# hd-gs-alt.net
KiCad netlist of a schematic drawn in EAGLE
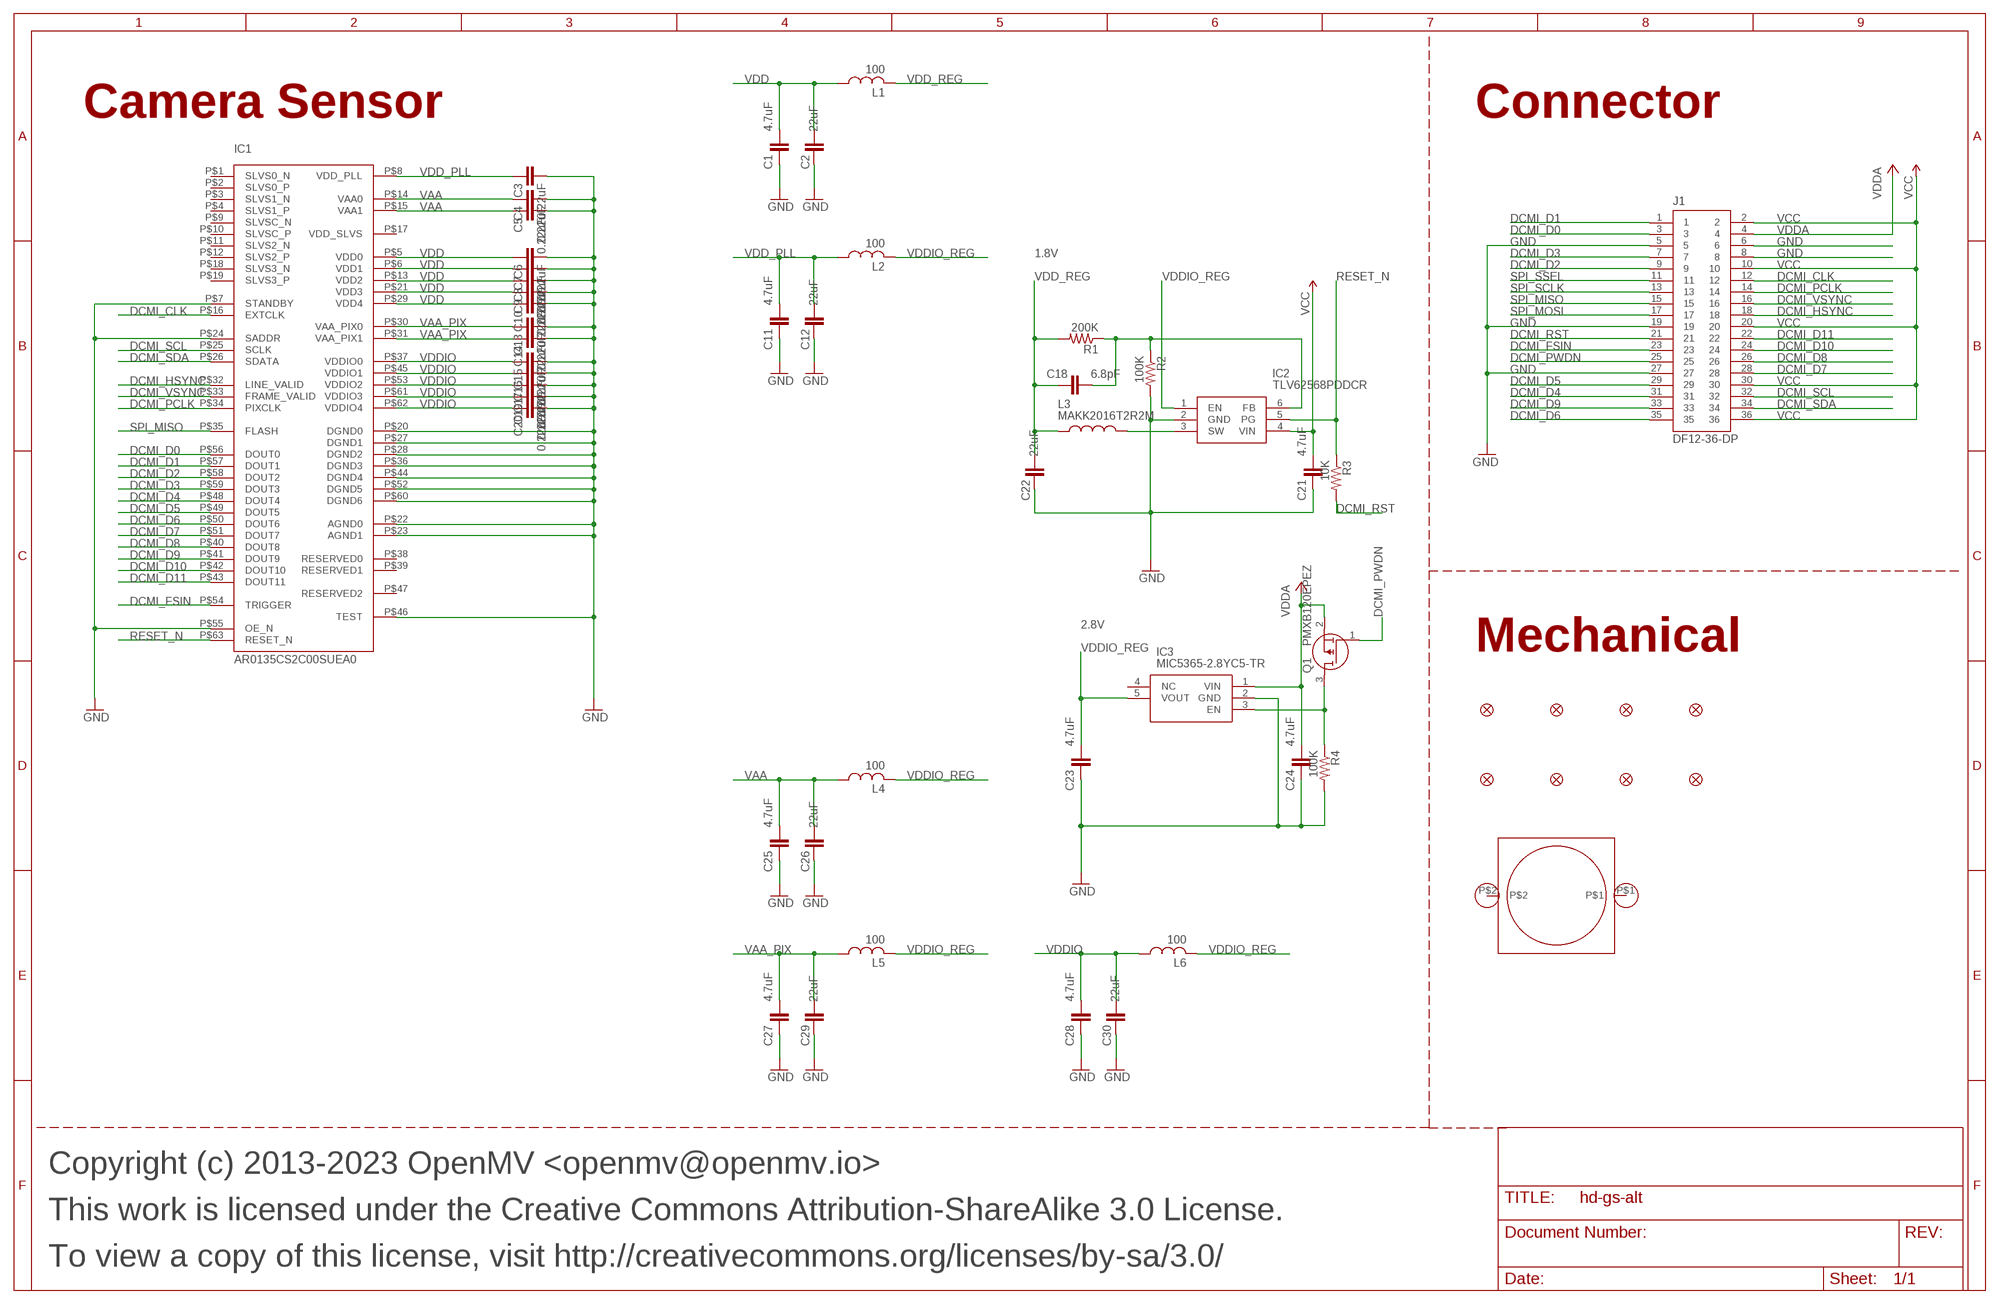
[diagram p0: schematic, sheet 1]

(export (version "E")
  (design (tool "Eeschema 10.0.6"))
  (components
    (comp (ref "C1")
      (value "4.7uF")
      (footprint "eagle-import:0402")
      (fields (field (name "MPN") "JMK105BBJ475MV-F"))
      (libsource (lib "eagle-import") (part "CAP_0402"))
    )
    (comp (ref "C2")
      (value "22uF")
      (footprint "eagle-import:0805")
      (fields (field (name "MPN") "CL21A226MQQNNNE"))
      (libsource (lib "eagle-import") (part "22UF-0805-6.3V-20%"))
    )
    (comp (ref "C3")
      (value "0.22uF")
      (footprint "eagle-import:C0201")
      (fields (field (name "MPN") "GRM033R60J224ME15D"))
      (libsource (lib "eagle-import") (part "C-EUC0201"))
    )
    (comp (ref "C4")
      (value "0.22uF")
      (footprint "eagle-import:C0201")
      (fields (field (name "MPN") "GRM033R60J224ME15D"))
      (libsource (lib "eagle-import") (part "C-EUC0201"))
    )
    (comp (ref "C5")
      (value "0.22uF")
      (footprint "eagle-import:C0201")
      (fields (field (name "MPN") "GRM033R60J224ME15D"))
      (libsource (lib "eagle-import") (part "C-EUC0201"))
    )
    (comp (ref "C6")
      (value "0.22uF")
      (footprint "eagle-import:C0201")
      (fields (field (name "MPN") "GRM033R60J224ME15D"))
      (libsource (lib "eagle-import") (part "C-EUC0201"))
    )
    (comp (ref "C7")
      (value "0.22uF")
      (footprint "eagle-import:C0201")
      (fields (field (name "MPN") "GRM033R60J224ME15D"))
      (libsource (lib "eagle-import") (part "C-EUC0201"))
    )
    (comp (ref "C8")
      (value "0.22uF")
      (footprint "eagle-import:C0201")
      (fields (field (name "MPN") "GRM033R60J224ME15D"))
      (libsource (lib "eagle-import") (part "C-EUC0201"))
    )
    (comp (ref "C9")
      (value "0.22uF")
      (footprint "eagle-import:C0201")
      (fields (field (name "MPN") "GRM033R60J224ME15D"))
      (libsource (lib "eagle-import") (part "C-EUC0201"))
    )
    (comp (ref "C10")
      (value "0.22uF")
      (footprint "eagle-import:C0201")
      (fields (field (name "MPN") "GRM033R60J224ME15D"))
      (libsource (lib "eagle-import") (part "C-EUC0201"))
    )
    (comp (ref "C11")
      (value "4.7uF")
      (footprint "eagle-import:0402")
      (fields (field (name "MPN") "JMK105BBJ475MV-F"))
      (libsource (lib "eagle-import") (part "CAP_0402"))
    )
    (comp (ref "C12")
      (value "22uF")
      (footprint "eagle-import:0805")
      (fields (field (name "MPN") "CL21A226MQQNNNE"))
      (libsource (lib "eagle-import") (part "22UF-0805-6.3V-20%"))
    )
    (comp (ref "C13")
      (value "0.22uF")
      (footprint "eagle-import:C0201")
      (fields (field (name "MPN") "GRM033R60J224ME15D"))
      (libsource (lib "eagle-import") (part "C-EUC0201"))
    )
    (comp (ref "C14")
      (value "0.22uF")
      (footprint "eagle-import:C0201")
      (fields (field (name "MPN") "GRM033R60J224ME15D"))
      (libsource (lib "eagle-import") (part "C-EUC0201"))
    )
    (comp (ref "C15")
      (value "0.22uF")
      (footprint "eagle-import:C0201")
      (fields (field (name "MPN") "GRM033R60J224ME15D"))
      (libsource (lib "eagle-import") (part "C-EUC0201"))
    )
    (comp (ref "C16")
      (value "0.22uF")
      (footprint "eagle-import:C0201")
      (fields (field (name "MPN") "GRM033R60J224ME15D"))
      (libsource (lib "eagle-import") (part "C-EUC0201"))
    )
    (comp (ref "C17")
      (value "0.22uF")
      (footprint "eagle-import:C0201")
      (fields (field (name "MPN") "GRM033R60J224ME15D"))
      (libsource (lib "eagle-import") (part "C-EUC0201"))
    )
    (comp (ref "C18")
      (value "6.8pF")
      (footprint "eagle-import:0402")
      (fields (field (name "MPN") "GRM1555C1H6R8DA01D"))
      (libsource (lib "eagle-import") (part "CAP_0402"))
    )
    (comp (ref "C19")
      (value "0.22uF")
      (footprint "eagle-import:C0201")
      (fields (field (name "MPN") "GRM033R60J224ME15D"))
      (libsource (lib "eagle-import") (part "C-EUC0201"))
    )
    (comp (ref "C20")
      (value "0.22uF")
      (footprint "eagle-import:C0201")
      (fields (field (name "MPN") "GRM033R60J224ME15D"))
      (libsource (lib "eagle-import") (part "C-EUC0201"))
    )
    (comp (ref "C21")
      (value "4.7uF")
      (footprint "eagle-import:0402")
      (fields (field (name "MPN") "JMK105BBJ475MV-F"))
      (libsource (lib "eagle-import") (part "CAP_0402"))
    )
    (comp (ref "C22")
      (value "22uF")
      (footprint "eagle-import:0805")
      (fields (field (name "MPN") "CL21A226MQQNNNE"))
      (libsource (lib "eagle-import") (part "22UF-0805-6.3V-20%"))
    )
    (comp (ref "C23")
      (value "4.7uF")
      (footprint "eagle-import:0402")
      (fields (field (name "MPN") "JMK105BBJ475MV-F"))
      (libsource (lib "eagle-import") (part "CAP_0402"))
    )
    (comp (ref "C24")
      (value "4.7uF")
      (footprint "eagle-import:0402")
      (fields (field (name "MPN") "JMK105BBJ475MV-F"))
      (libsource (lib "eagle-import") (part "CAP_0402"))
    )
    (comp (ref "C25")
      (value "4.7uF")
      (footprint "eagle-import:0402")
      (fields (field (name "MPN") "JMK105BBJ475MV-F"))
      (libsource (lib "eagle-import") (part "CAP_0402"))
    )
    (comp (ref "C26")
      (value "22uF")
      (footprint "eagle-import:0805")
      (fields (field (name "MPN") "CL21A226MQQNNNE"))
      (libsource (lib "eagle-import") (part "22UF-0805-6.3V-20%"))
    )
    (comp (ref "C27")
      (value "4.7uF")
      (footprint "eagle-import:0402")
      (fields (field (name "MPN") "JMK105BBJ475MV-F"))
      (libsource (lib "eagle-import") (part "CAP_0402"))
    )
    (comp (ref "C28")
      (value "4.7uF")
      (footprint "eagle-import:0402")
      (fields (field (name "MPN") "JMK105BBJ475MV-F"))
      (libsource (lib "eagle-import") (part "CAP_0402"))
    )
    (comp (ref "C29")
      (value "22uF")
      (footprint "eagle-import:0805")
      (fields (field (name "MPN") "CL21A226MQQNNNE"))
      (libsource (lib "eagle-import") (part "22UF-0805-6.3V-20%"))
    )
    (comp (ref "C30")
      (value "22uF")
      (footprint "eagle-import:0805")
      (fields (field (name "MPN") "CL21A226MQQNNNE"))
      (libsource (lib "eagle-import") (part "22UF-0805-6.3V-20%"))
    )
    (comp (ref "FD1")
      (value "FIDUCIAL1X2")
      (footprint "eagle-import:FIDUCIAL-1X2")
      (libsource (lib "eagle-import") (part "FIDUCIAL1X2"))
    )
    (comp (ref "FD2")
      (value "FIDUCIAL1X2")
      (footprint "eagle-import:FIDUCIAL-1X2")
      (libsource (lib "eagle-import") (part "FIDUCIAL1X2"))
    )
    (comp (ref "FD3")
      (value "FIDUCIAL1X2")
      (footprint "eagle-import:FIDUCIAL-1X2")
      (libsource (lib "eagle-import") (part "FIDUCIAL1X2"))
    )
    (comp (ref "FD4")
      (value "FIDUCIAL1X2")
      (footprint "eagle-import:FIDUCIAL-1X2")
      (libsource (lib "eagle-import") (part "FIDUCIAL1X2"))
    )
    (comp (ref "FD5")
      (value "FIDUCIAL1X2")
      (footprint "eagle-import:FIDUCIAL-1X2")
      (libsource (lib "eagle-import") (part "FIDUCIAL1X2"))
    )
    (comp (ref "FD6")
      (value "FIDUCIAL1X2")
      (footprint "eagle-import:FIDUCIAL-1X2")
      (libsource (lib "eagle-import") (part "FIDUCIAL1X2"))
    )
    (comp (ref "FD7")
      (value "FIDUCIAL1X2")
      (footprint "eagle-import:FIDUCIAL-1X2")
      (libsource (lib "eagle-import") (part "FIDUCIAL1X2"))
    )
    (comp (ref "FD8")
      (value "FIDUCIAL1X2")
      (footprint "eagle-import:FIDUCIAL-1X2")
      (libsource (lib "eagle-import") (part "FIDUCIAL1X2"))
    )
    (comp (ref "H1")
      (value "LENSMOUNT20MM")
      (footprint "eagle-import:LENSMOUNT-20MM")
      (libsource (lib "eagle-import") (part "LENSMOUNT20MM"))
    )
    (comp (ref "IC1")
      (value "AR0135CS2C00SUEA0")
      (footprint "eagle-import:AR0135CS2C00SUEA0")
      (fields (field (name "MPN") "AR0135CS2C00SUEA0-DRBR"))
      (libsource (lib "eagle-import") (part "AR0135CS2C00SUEA0"))
    )
    (comp (ref "IC2")
      (value "TLV62568PDDCR")
      (footprint "eagle-import:SOT95P280X110-6N")
      (fields (field (name "MOUSER_PART_NUMBER") "595-TLV62568PDDCR"))
      (libsource (lib "eagle-import") (part "TLV62568PDDCR"))
    )
    (comp (ref "IC3")
      (value "MIC5365-2.8YC5-TR")
      (footprint "eagle-import:SOT65P210X110-5N")
      (fields (field (name "MOUSER_PART_NUMBER") "998-MIC5365-2.8YC5TR"))
      (libsource (lib "eagle-import") (part "MIC5365-2.8YC5-TR"))
    )
    (comp (ref "J1")
      (value "DF12-36-DP")
      (footprint "eagle-import:DF12-36-DP")
      (fields (field (name "MPN") "DF12NB(3.0)-36DP-0.5V(51)"))
      (libsource (lib "eagle-import") (part "DF12-36-DP"))
    )
    (comp (ref "L1")
      (value "100")
      (footprint "eagle-import:0402")
      (fields (field (name "MPN") "MFBM1V1005-101-R"))
      (libsource (lib "eagle-import") (part "INDUCTOR_0402"))
    )
    (comp (ref "L2")
      (value "100")
      (footprint "eagle-import:0402")
      (fields (field (name "MPN") "MFBM1V1005-101-R"))
      (libsource (lib "eagle-import") (part "INDUCTOR_0402"))
    )
    (comp (ref "L3")
      (value "MAKK2016T2R2M")
      (footprint "eagle-import:INDC2016X100N")
      (fields (field (name "MF") "Taiyo Yuden"))
      (libsource (lib "eagle-import") (part "MAKK2016T2R2M"))
    )
    (comp (ref "L4")
      (value "100")
      (footprint "eagle-import:0402")
      (fields (field (name "MPN") "MFBM1V1005-101-R"))
      (libsource (lib "eagle-import") (part "INDUCTOR_0402"))
    )
    (comp (ref "L5")
      (value "100")
      (footprint "eagle-import:0402")
      (fields (field (name "MPN") "MFBM1V1005-101-R"))
      (libsource (lib "eagle-import") (part "INDUCTOR_0402"))
    )
    (comp (ref "L6")
      (value "100")
      (footprint "eagle-import:0402")
      (fields (field (name "MPN") "MFBM1V1005-101-R"))
      (libsource (lib "eagle-import") (part "INDUCTOR_0402"))
    )
    (comp (ref "Q1")
      (value "PMXB120EPEZ")
      (footprint "eagle-import:PMXB120EPEZ")
      (fields (field (name "MOUSER_PART_NUMBER") "771-PMXB120EPEZ"))
      (libsource (lib "eagle-import") (part "PMXB120EPEZ"))
    )
    (comp (ref "R1")
      (value "200K")
      (footprint "eagle-import:R0402")
      (fields (field (name "MPN") "CRCW0402200KFKEDC"))
      (libsource (lib "eagle-import") (part "R-US_R0402"))
    )
    (comp (ref "R2")
      (value "100K")
      (footprint "eagle-import:R0402")
      (fields (field (name "MPN") "AC0402FR-07100KL"))
      (libsource (lib "eagle-import") (part "R-US_R0402"))
    )
    (comp (ref "R3")
      (value "10K")
      (footprint "eagle-import:R0402")
      (fields (field (name "MPN") "AC0402FR-1310KL"))
      (libsource (lib "eagle-import") (part "R-US_R0402"))
    )
    (comp (ref "R4")
      (value "100K")
      (footprint "eagle-import:R0402")
      (fields (field (name "MPN") "AC0402FR-07100KL"))
      (libsource (lib "eagle-import") (part "R-US_R0402"))
    )
  )
  (nets
    (net (code "1") (name "/DCMI_CLK") (class "Default")
      (node (ref "IC1") (pin "P$16") (pinfunction "EXTCLK_P$16") (pintype "bidirectional"))
      (node (ref "J1") (pin "12") (pinfunction "12_12") (pintype "bidirectional"))
    )
    (net (code "2") (name "/DCMI_D0") (class "Default")
      (node (ref "IC1") (pin "P$56") (pinfunction "DOUT0_P$56") (pintype "bidirectional"))
      (node (ref "J1") (pin "3") (pinfunction "3_3") (pintype "bidirectional"))
    )
    (net (code "3") (name "/DCMI_D1") (class "Default")
      (node (ref "IC1") (pin "P$57") (pinfunction "DOUT1_P$57") (pintype "bidirectional"))
      (node (ref "J1") (pin "1") (pinfunction "1_1") (pintype "bidirectional"))
    )
    (net (code "4") (name "/DCMI_D2") (class "Default")
      (node (ref "IC1") (pin "P$58") (pinfunction "DOUT2_P$58") (pintype "bidirectional"))
      (node (ref "J1") (pin "9") (pinfunction "9_9") (pintype "bidirectional"))
    )
    (net (code "5") (name "/DCMI_D3") (class "Default")
      (node (ref "IC1") (pin "P$59") (pinfunction "DOUT3_P$59") (pintype "bidirectional"))
      (node (ref "J1") (pin "7") (pinfunction "7_7") (pintype "bidirectional"))
    )
    (net (code "6") (name "/DCMI_D4") (class "Default")
      (node (ref "IC1") (pin "P$48") (pinfunction "DOUT4_P$48") (pintype "bidirectional"))
      (node (ref "J1") (pin "31") (pinfunction "31_31") (pintype "bidirectional"))
    )
    (net (code "7") (name "/DCMI_D5") (class "Default")
      (node (ref "IC1") (pin "P$49") (pinfunction "DOUT5_P$49") (pintype "bidirectional"))
      (node (ref "J1") (pin "29") (pinfunction "29_29") (pintype "bidirectional"))
    )
    (net (code "8") (name "/DCMI_D6") (class "Default")
      (node (ref "IC1") (pin "P$50") (pinfunction "DOUT6_P$50") (pintype "bidirectional"))
      (node (ref "J1") (pin "35") (pinfunction "35_35") (pintype "bidirectional"))
    )
    (net (code "9") (name "/DCMI_D7") (class "Default")
      (node (ref "IC1") (pin "P$51") (pinfunction "DOUT7_P$51") (pintype "bidirectional"))
      (node (ref "J1") (pin "28") (pinfunction "28_28") (pintype "bidirectional"))
    )
    (net (code "10") (name "/DCMI_D8") (class "Default")
      (node (ref "IC1") (pin "P$40") (pinfunction "DOUT8_P$40") (pintype "bidirectional"))
      (node (ref "J1") (pin "26") (pinfunction "26_26") (pintype "bidirectional"))
    )
    (net (code "11") (name "/DCMI_D9") (class "Default")
      (node (ref "IC1") (pin "P$41") (pinfunction "DOUT9_P$41") (pintype "bidirectional"))
      (node (ref "J1") (pin "33") (pinfunction "33_33") (pintype "bidirectional"))
    )
    (net (code "12") (name "/DCMI_D10") (class "Default")
      (node (ref "IC1") (pin "P$42") (pinfunction "DOUT10_P$42") (pintype "bidirectional"))
      (node (ref "J1") (pin "24") (pinfunction "24_24") (pintype "bidirectional"))
    )
    (net (code "13") (name "/DCMI_D11") (class "Default")
      (node (ref "IC1") (pin "P$43") (pinfunction "DOUT11_P$43") (pintype "bidirectional"))
      (node (ref "J1") (pin "22") (pinfunction "22_22") (pintype "bidirectional"))
    )
    (net (code "14") (name "/DCMI_FSIN") (class "Default")
      (node (ref "IC1") (pin "P$54") (pinfunction "TRIGGER_P$54") (pintype "bidirectional"))
      (node (ref "J1") (pin "23") (pinfunction "23_23") (pintype "bidirectional"))
    )
    (net (code "15") (name "/DCMI_HSYNC") (class "Default")
      (node (ref "IC1") (pin "P$32") (pinfunction "LINE_VALID_P$32") (pintype "bidirectional"))
      (node (ref "J1") (pin "18") (pinfunction "18_18") (pintype "bidirectional"))
    )
    (net (code "16") (name "/DCMI_PCLK") (class "Default")
      (node (ref "IC1") (pin "P$34") (pinfunction "PIXCLK_P$34") (pintype "bidirectional"))
      (node (ref "J1") (pin "14") (pinfunction "14_14") (pintype "bidirectional"))
    )
    (net (code "17") (name "/DCMI_PWDN") (class "Default")
      (node (ref "J1") (pin "25") (pinfunction "25_25") (pintype "bidirectional"))
      (node (ref "Q1") (pin "1") (pinfunction "G_1") (pintype "bidirectional"))
    )
    (net (code "18") (name "/DCMI_RST") (class "Default")
      (node (ref "J1") (pin "21") (pinfunction "21_21") (pintype "bidirectional"))
      (node (ref "R3") (pin "2") (pinfunction "2_2") (pintype "passive"))
    )
    (net (code "19") (name "/DCMI_SCL") (class "Default")
      (node (ref "IC1") (pin "P$25") (pinfunction "SCLK_P$25") (pintype "bidirectional"))
      (node (ref "J1") (pin "32") (pinfunction "32_32") (pintype "bidirectional"))
    )
    (net (code "20") (name "/DCMI_SDA") (class "Default")
      (node (ref "IC1") (pin "P$26") (pinfunction "SDATA_P$26") (pintype "bidirectional"))
      (node (ref "J1") (pin "34") (pinfunction "34_34") (pintype "bidirectional"))
    )
    (net (code "21") (name "/DCMI_VSYNC") (class "Default")
      (node (ref "IC1") (pin "P$33") (pinfunction "FRAME_VALID_P$33") (pintype "bidirectional"))
      (node (ref "J1") (pin "16") (pinfunction "16_16") (pintype "bidirectional"))
    )
    (net (code "22") (name "/P$1") (class "Default")
      (node (ref "H1") (pin "P$1") (pinfunction "P$1_P$1") (pintype "power_in"))
    )
    (net (code "23") (name "/P$2") (class "Default")
      (node (ref "H1") (pin "P$2") (pinfunction "P$2_P$2") (pintype "power_in"))
    )
    (net (code "24") (name "/RESET_N") (class "Default")
      (node (ref "IC1") (pin "P$63") (pinfunction "RESET_N_P$63") (pintype "bidirectional"))
      (node (ref "IC2") (pin "5") (pinfunction "PG_5") (pintype "bidirectional"))
      (node (ref "R3") (pin "1") (pinfunction "1_1") (pintype "passive"))
    )
    (net (code "25") (name "/SPI_MISO") (class "Default")
      (node (ref "IC1") (pin "P$35") (pinfunction "FLASH_P$35") (pintype "bidirectional"))
      (node (ref "J1") (pin "15") (pinfunction "15_15") (pintype "bidirectional"))
    )
    (net (code "26") (name "/SPI_MOSI") (class "Default")
      (node (ref "J1") (pin "17") (pinfunction "17_17") (pintype "bidirectional"))
    )
    (net (code "27") (name "/SPI_SCLK") (class "Default")
      (node (ref "J1") (pin "13") (pinfunction "13_13") (pintype "bidirectional"))
    )
    (net (code "28") (name "/SPI_SSEL") (class "Default")
      (node (ref "J1") (pin "11") (pinfunction "11_11") (pintype "bidirectional"))
    )
    (net (code "29") (name "/VAA") (class "Default")
      (node (ref "C25") (pin "2") (pinfunction "2_2") (pintype "passive"))
      (node (ref "C26") (pin "2") (pinfunction "2_2") (pintype "passive"))
      (node (ref "C4") (pin "1") (pinfunction "1_1") (pintype "passive"))
      (node (ref "C5") (pin "1") (pinfunction "1_1") (pintype "passive"))
      (node (ref "IC1") (pin "P$14") (pinfunction "VAA0_P$14") (pintype "bidirectional"))
      (node (ref "IC1") (pin "P$15") (pinfunction "VAA1_P$15") (pintype "bidirectional"))
      (node (ref "L4") (pin "1") (pinfunction "P$1_1") (pintype "passive"))
    )
    (net (code "30") (name "/VAA_PIX") (class "Default")
      (node (ref "C13") (pin "1") (pinfunction "1_1") (pintype "passive"))
      (node (ref "C14") (pin "1") (pinfunction "1_1") (pintype "passive"))
      (node (ref "C27") (pin "2") (pinfunction "2_2") (pintype "passive"))
      (node (ref "C29") (pin "2") (pinfunction "2_2") (pintype "passive"))
      (node (ref "IC1") (pin "P$30") (pinfunction "VAA_PIX0_P$30") (pintype "bidirectional"))
      (node (ref "IC1") (pin "P$31") (pinfunction "VAA_PIX1_P$31") (pintype "bidirectional"))
      (node (ref "L5") (pin "1") (pinfunction "P$1_1") (pintype "passive"))
    )
    (net (code "31") (name "/VDD") (class "Default")
      (node (ref "C1") (pin "2") (pinfunction "2_2") (pintype "passive"))
      (node (ref "C10") (pin "1") (pinfunction "1_1") (pintype "passive"))
      (node (ref "C2") (pin "2") (pinfunction "2_2") (pintype "passive"))
      (node (ref "C6") (pin "1") (pinfunction "1_1") (pintype "passive"))
      (node (ref "C7") (pin "1") (pinfunction "1_1") (pintype "passive"))
      (node (ref "C8") (pin "1") (pinfunction "1_1") (pintype "passive"))
      (node (ref "C9") (pin "1") (pinfunction "1_1") (pintype "passive"))
      (node (ref "IC1") (pin "P$13") (pinfunction "VDD2_P$13") (pintype "bidirectional"))
      (node (ref "IC1") (pin "P$21") (pinfunction "VDD3_P$21") (pintype "bidirectional"))
      (node (ref "IC1") (pin "P$29") (pinfunction "VDD4_P$29") (pintype "bidirectional"))
      (node (ref "IC1") (pin "P$5") (pinfunction "VDD0_P$5") (pintype "bidirectional"))
      (node (ref "IC1") (pin "P$6") (pinfunction "VDD1_P$6") (pintype "bidirectional"))
      (node (ref "L1") (pin "1") (pinfunction "P$1_1") (pintype "passive"))
    )
    (net (code "32") (name "/VDDIO") (class "Default")
      (node (ref "C15") (pin "1") (pinfunction "1_1") (pintype "passive"))
      (node (ref "C16") (pin "1") (pinfunction "1_1") (pintype "passive"))
      (node (ref "C17") (pin "1") (pinfunction "1_1") (pintype "passive"))
      (node (ref "C19") (pin "1") (pinfunction "1_1") (pintype "passive"))
      (node (ref "C20") (pin "1") (pinfunction "1_1") (pintype "passive"))
      (node (ref "C28") (pin "2") (pinfunction "2_2") (pintype "passive"))
      (node (ref "C30") (pin "2") (pinfunction "2_2") (pintype "passive"))
      (node (ref "IC1") (pin "P$37") (pinfunction "VDDIO0_P$37") (pintype "bidirectional"))
      (node (ref "IC1") (pin "P$45") (pinfunction "VDDIO1_P$45") (pintype "bidirectional"))
      (node (ref "IC1") (pin "P$53") (pinfunction "VDDIO2_P$53") (pintype "bidirectional"))
      (node (ref "IC1") (pin "P$61") (pinfunction "VDDIO3_P$61") (pintype "bidirectional"))
      (node (ref "IC1") (pin "P$62") (pinfunction "VDDIO4_P$62") (pintype "bidirectional"))
      (node (ref "L6") (pin "1") (pinfunction "P$1_1") (pintype "passive"))
    )
    (net (code "33") (name "/VDDIO_REG") (class "Default")
      (node (ref "C23") (pin "2") (pinfunction "2_2") (pintype "passive"))
      (node (ref "IC2") (pin "1") (pinfunction "EN_1") (pintype "bidirectional"))
      (node (ref "IC3") (pin "5") (pinfunction "VOUT_5") (pintype "bidirectional"))
      (node (ref "L2") (pin "2") (pinfunction "P$2_2") (pintype "passive"))
      (node (ref "L4") (pin "2") (pinfunction "P$2_2") (pintype "passive"))
      (node (ref "L5") (pin "2") (pinfunction "P$2_2") (pintype "passive"))
      (node (ref "L6") (pin "2") (pinfunction "P$2_2") (pintype "passive"))
    )
    (net (code "34") (name "/VDD_PLL") (class "Default")
      (node (ref "C11") (pin "2") (pinfunction "2_2") (pintype "passive"))
      (node (ref "C12") (pin "2") (pinfunction "2_2") (pintype "passive"))
      (node (ref "C3") (pin "1") (pinfunction "1_1") (pintype "passive"))
      (node (ref "IC1") (pin "P$8") (pinfunction "VDD_PLL_P$8") (pintype "bidirectional"))
      (node (ref "L2") (pin "1") (pinfunction "P$1_1") (pintype "passive"))
    )
    (net (code "35") (name "/VDD_REG") (class "Default")
      (node (ref "C18") (pin "1") (pinfunction "1_1") (pintype "passive"))
      (node (ref "C22") (pin "2") (pinfunction "2_2") (pintype "passive"))
      (node (ref "L1") (pin "2") (pinfunction "P$2_2") (pintype "passive"))
      (node (ref "L3") (pin "1") (pinfunction "1_1") (pintype "passive"))
      (node (ref "R1") (pin "2") (pinfunction "2_2") (pintype "passive"))
    )
    (net (code "36") (name "GND") (class "Default")
      (node (ref "C1") (pin "1") (pinfunction "1_1") (pintype "passive"))
      (node (ref "C10") (pin "2") (pinfunction "2_2") (pintype "passive"))
      (node (ref "C11") (pin "1") (pinfunction "1_1") (pintype "passive"))
      (node (ref "C12") (pin "1") (pinfunction "1_1") (pintype "passive"))
      (node (ref "C13") (pin "2") (pinfunction "2_2") (pintype "passive"))
      (node (ref "C14") (pin "2") (pinfunction "2_2") (pintype "passive"))
      (node (ref "C15") (pin "2") (pinfunction "2_2") (pintype "passive"))
      (node (ref "C16") (pin "2") (pinfunction "2_2") (pintype "passive"))
      (node (ref "C17") (pin "2") (pinfunction "2_2") (pintype "passive"))
      (node (ref "C19") (pin "2") (pinfunction "2_2") (pintype "passive"))
      (node (ref "C2") (pin "1") (pinfunction "1_1") (pintype "passive"))
      (node (ref "C20") (pin "2") (pinfunction "2_2") (pintype "passive"))
      (node (ref "C21") (pin "1") (pinfunction "1_1") (pintype "passive"))
      (node (ref "C22") (pin "1") (pinfunction "1_1") (pintype "passive"))
      (node (ref "C23") (pin "1") (pinfunction "1_1") (pintype "passive"))
      (node (ref "C24") (pin "1") (pinfunction "1_1") (pintype "passive"))
      (node (ref "C25") (pin "1") (pinfunction "1_1") (pintype "passive"))
      (node (ref "C26") (pin "1") (pinfunction "1_1") (pintype "passive"))
      (node (ref "C27") (pin "1") (pinfunction "1_1") (pintype "passive"))
      (node (ref "C28") (pin "1") (pinfunction "1_1") (pintype "passive"))
      (node (ref "C29") (pin "1") (pinfunction "1_1") (pintype "passive"))
      (node (ref "C3") (pin "2") (pinfunction "2_2") (pintype "passive"))
      (node (ref "C30") (pin "1") (pinfunction "1_1") (pintype "passive"))
      (node (ref "C4") (pin "2") (pinfunction "2_2") (pintype "passive"))
      (node (ref "C5") (pin "2") (pinfunction "2_2") (pintype "passive"))
      (node (ref "C6") (pin "2") (pinfunction "2_2") (pintype "passive"))
      (node (ref "C7") (pin "2") (pinfunction "2_2") (pintype "passive"))
      (node (ref "C8") (pin "2") (pinfunction "2_2") (pintype "passive"))
      (node (ref "C9") (pin "2") (pinfunction "2_2") (pintype "passive"))
      (node (ref "IC1") (pin "P$20") (pinfunction "DGND0_P$20") (pintype "bidirectional"))
      (node (ref "IC1") (pin "P$22") (pinfunction "AGND0_P$22") (pintype "bidirectional"))
      (node (ref "IC1") (pin "P$23") (pinfunction "AGND1_P$23") (pintype "bidirectional"))
      (node (ref "IC1") (pin "P$24") (pinfunction "SADDR_P$24") (pintype "bidirectional"))
      (node (ref "IC1") (pin "P$27") (pinfunction "DGND1_P$27") (pintype "bidirectional"))
      (node (ref "IC1") (pin "P$28") (pinfunction "DGND2_P$28") (pintype "bidirectional"))
      (node (ref "IC1") (pin "P$36") (pinfunction "DGND3_P$36") (pintype "bidirectional"))
      (node (ref "IC1") (pin "P$44") (pinfunction "DGND4_P$44") (pintype "bidirectional"))
      (node (ref "IC1") (pin "P$46") (pinfunction "TEST_P$46") (pintype "bidirectional"))
      (node (ref "IC1") (pin "P$52") (pinfunction "DGND5_P$52") (pintype "bidirectional"))
      (node (ref "IC1") (pin "P$55") (pinfunction "OE_N_P$55") (pintype "bidirectional"))
      (node (ref "IC1") (pin "P$60") (pinfunction "DGND6_P$60") (pintype "bidirectional"))
      (node (ref "IC1") (pin "P$7") (pinfunction "STANDBY_P$7") (pintype "bidirectional"))
      (node (ref "IC2") (pin "2") (pinfunction "GND_2") (pintype "bidirectional"))
      (node (ref "IC3") (pin "2") (pinfunction "GND_2") (pintype "bidirectional"))
      (node (ref "J1") (pin "19") (pinfunction "19_19") (pintype "bidirectional"))
      (node (ref "J1") (pin "27") (pinfunction "27_27") (pintype "bidirectional"))
      (node (ref "J1") (pin "5") (pinfunction "5_5") (pintype "bidirectional"))
      (node (ref "J1") (pin "6") (pinfunction "6_6") (pintype "bidirectional"))
      (node (ref "J1") (pin "8") (pinfunction "8_8") (pintype "bidirectional"))
      (node (ref "R2") (pin "2") (pinfunction "2_2") (pintype "passive"))
      (node (ref "R4") (pin "2") (pinfunction "2_2") (pintype "passive"))
    )
    (net (code "37") (name "Net-(IC2-FB)") (class "Default")
      (node (ref "C18") (pin "2") (pinfunction "2_2") (pintype "passive"))
      (node (ref "IC2") (pin "6") (pinfunction "FB_6") (pintype "bidirectional"))
      (node (ref "R1") (pin "1") (pinfunction "1_1") (pintype "passive"))
      (node (ref "R2") (pin "1") (pinfunction "1_1") (pintype "passive"))
    )
    (net (code "38") (name "Net-(IC2-SW)") (class "Default")
      (node (ref "IC2") (pin "3") (pinfunction "SW_3") (pintype "bidirectional"))
      (node (ref "L3") (pin "2") (pinfunction "2_2") (pintype "passive"))
    )
    (net (code "39") (name "Net-(IC3-EN)") (class "Default")
      (node (ref "IC3") (pin "3") (pinfunction "EN_3") (pintype "bidirectional"))
      (node (ref "Q1") (pin "3") (pinfunction "D_3") (pintype "bidirectional"))
      (node (ref "R4") (pin "1") (pinfunction "1_1") (pintype "passive"))
    )
    (net (code "40") (name "VCC") (class "Default")
      (node (ref "C21") (pin "2") (pinfunction "2_2") (pintype "passive"))
      (node (ref "IC2") (pin "4") (pinfunction "VIN_4") (pintype "bidirectional"))
      (node (ref "J1") (pin "10") (pinfunction "10_10") (pintype "bidirectional"))
      (node (ref "J1") (pin "2") (pinfunction "2_2") (pintype "bidirectional"))
      (node (ref "J1") (pin "20") (pinfunction "20_20") (pintype "bidirectional"))
      (node (ref "J1") (pin "30") (pinfunction "30_30") (pintype "bidirectional"))
      (node (ref "J1") (pin "36") (pinfunction "36_36") (pintype "bidirectional"))
    )
    (net (code "41") (name "VDDA") (class "Default")
      (node (ref "C24") (pin "2") (pinfunction "2_2") (pintype "passive"))
      (node (ref "IC3") (pin "1") (pinfunction "VIN_1") (pintype "bidirectional"))
      (node (ref "J1") (pin "4") (pinfunction "4_4") (pintype "bidirectional"))
      (node (ref "Q1") (pin "2") (pinfunction "S_2") (pintype "bidirectional"))
    )
    (net (code "42") (name "unconnected-(IC1-RESERVED0-PadP$38)") (class "Default")
      (node (ref "IC1") (pin "P$38") (pinfunction "RESERVED0_P$38") (pintype "bidirectional"))
    )
    (net (code "43") (name "unconnected-(IC1-RESERVED1-PadP$39)") (class "Default")
      (node (ref "IC1") (pin "P$39") (pinfunction "RESERVED1_P$39") (pintype "bidirectional"))
    )
    (net (code "44") (name "unconnected-(IC1-RESERVED2-PadP$47)") (class "Default")
      (node (ref "IC1") (pin "P$47") (pinfunction "RESERVED2_P$47") (pintype "bidirectional"))
    )
    (net (code "45") (name "unconnected-(IC1-SLVS0_N-PadP$1)") (class "Default")
      (node (ref "IC1") (pin "P$1") (pinfunction "SLVS0_N_P$1") (pintype "bidirectional"))
    )
    (net (code "46") (name "unconnected-(IC1-SLVS0_P-PadP$2)") (class "Default")
      (node (ref "IC1") (pin "P$2") (pinfunction "SLVS0_P_P$2") (pintype "bidirectional"))
    )
    (net (code "47") (name "unconnected-(IC1-SLVS1_N-PadP$3)") (class "Default")
      (node (ref "IC1") (pin "P$3") (pinfunction "SLVS1_N_P$3") (pintype "bidirectional"))
    )
    (net (code "48") (name "unconnected-(IC1-SLVS1_P-PadP$4)") (class "Default")
      (node (ref "IC1") (pin "P$4") (pinfunction "SLVS1_P_P$4") (pintype "bidirectional"))
    )
    (net (code "49") (name "unconnected-(IC1-SLVS2_N-PadP$11)") (class "Default")
      (node (ref "IC1") (pin "P$11") (pinfunction "SLVS2_N_P$11") (pintype "bidirectional"))
    )
    (net (code "50") (name "unconnected-(IC1-SLVS2_P-PadP$12)") (class "Default")
      (node (ref "IC1") (pin "P$12") (pinfunction "SLVS2_P_P$12") (pintype "bidirectional"))
    )
    (net (code "51") (name "unconnected-(IC1-SLVS3_N-PadP$18)") (class "Default")
      (node (ref "IC1") (pin "P$18") (pinfunction "SLVS3_N_P$18") (pintype "bidirectional"))
    )
    (net (code "52") (name "unconnected-(IC1-SLVS3_P-PadP$19)") (class "Default")
      (node (ref "IC1") (pin "P$19") (pinfunction "SLVS3_P_P$19") (pintype "bidirectional"))
    )
    (net (code "53") (name "unconnected-(IC1-SLVSC_N-PadP$9)") (class "Default")
      (node (ref "IC1") (pin "P$9") (pinfunction "SLVSC_N_P$9") (pintype "bidirectional"))
    )
    (net (code "54") (name "unconnected-(IC1-SLVSC_P-PadP$10)") (class "Default")
      (node (ref "IC1") (pin "P$10") (pinfunction "SLVSC_P_P$10") (pintype "bidirectional"))
    )
    (net (code "55") (name "unconnected-(IC1-VDD_SLVS-PadP$17)") (class "Default")
      (node (ref "IC1") (pin "P$17") (pinfunction "VDD_SLVS_P$17") (pintype "bidirectional"))
    )
    (net (code "56") (name "unconnected-(IC3-NC-Pad4)") (class "Default")
      (node (ref "IC3") (pin "4") (pinfunction "NC_4") (pintype "no_connect"))
    )
  )
)
